# AT24C.net
KiCad netlist of a schematic drawn in Altium Designer
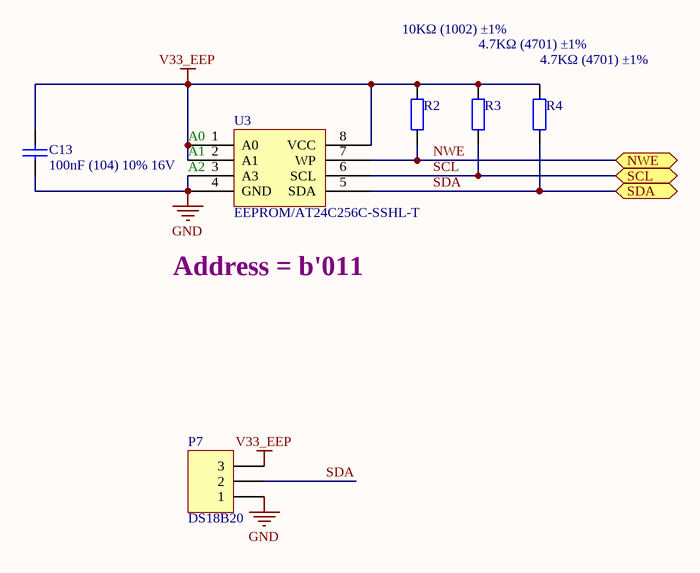
[diagram p0: AT24C.SchDoc]

(export (version "E")
  (design (tool "Eeschema 10.0.6"))
  (components
    (comp (ref "C13")
      (value "100nF (104) 10% 16V")
      (footprint "0402_C")
      (description "贴片电容")
      (libsource (lib "Miscellaneous Devices LC") (part "0402 100nF (104) 10% 16V"))
    )
    (comp (ref "P7")
      (value "DS18B20")
      (footprint "TO-92A")
      (description "Header, 3-Pin")
      (fields (field (name "PUBLISHER") "Altium Limited"))
      (libsource (lib "Miscellaneous Connectors") (part "Header 3"))
    )
    (comp (ref "R2")
      (value "10KΩ (1002) ±1%")
      (footprint "0402_R")
      (description "贴片电阻")
      (libsource (lib "Miscellaneous Devices LC") (part "0402 10KΩ (1002) 1%"))
    )
    (comp (ref "R3")
      (value "4.7KΩ (4701) ±1%")
      (footprint "0402_R")
      (description "贴片电阻")
      (libsource (lib "Miscellaneous Devices LC") (part "0402 4.7KΩ (4701) 1%"))
    )
    (comp (ref "R4")
      (value "4.7KΩ (4701) ±1%")
      (footprint "0402_R")
      (description "贴片电阻")
      (libsource (lib "Miscellaneous Devices LC") (part "0402 4.7KΩ (4701) 1%"))
    )
    (comp (ref "U3")
      (value "EEPROM/AT24C256C-SSHL-T")
      (footprint "SOIC-8_150mil")
      (description "EEPROM")
      (libsource (lib "Miscellaneous Devices LC") (part "EEPROM/AT24C256C-SSHL-T_[C6482]"))
    )
  )
  (nets
    (net (code "1") (name "/NWE") (class "Default")
      (node (ref "R2") (pin "1") (pinfunction "1_1") (pintype "passive"))
      (node (ref "U3") (pin "7") (pinfunction "WP_7") (pintype "passive"))
    )
    (net (code "2") (name "/SCL") (class "Default")
      (node (ref "R3") (pin "1") (pinfunction "1_1") (pintype "passive"))
      (node (ref "U3") (pin "6") (pinfunction "SCL_6") (pintype "passive"))
    )
    (net (code "3") (name "/SDA") (class "Default")
      (node (ref "P7") (pin "2") (pinfunction "2_2") (pintype "passive"))
      (node (ref "R4") (pin "1") (pinfunction "1_1") (pintype "passive"))
      (node (ref "U3") (pin "5") (pinfunction "SDA_5") (pintype "passive"))
    )
    (net (code "4") (name "GND") (class "Default")
      (node (ref "C13") (pin "1") (pinfunction "1_1") (pintype "passive"))
      (node (ref "P7") (pin "1") (pinfunction "1_1") (pintype "passive"))
      (node (ref "U3") (pin "3") (pinfunction "A3_3") (pintype "passive"))
      (node (ref "U3") (pin "4") (pinfunction "GND_4") (pintype "passive"))
    )
    (net (code "5") (name "V33_EEP") (class "Default")
      (node (ref "C13") (pin "2") (pinfunction "2_2") (pintype "passive"))
      (node (ref "P7") (pin "3") (pinfunction "3_3") (pintype "passive"))
      (node (ref "R2") (pin "2") (pinfunction "2_2") (pintype "passive"))
      (node (ref "R3") (pin "2") (pinfunction "2_2") (pintype "passive"))
      (node (ref "R4") (pin "2") (pinfunction "2_2") (pintype "passive"))
      (node (ref "U3") (pin "1") (pinfunction "A0_1") (pintype "passive"))
      (node (ref "U3") (pin "2") (pinfunction "A1_2") (pintype "passive"))
      (node (ref "U3") (pin "8") (pinfunction "VCC_8") (pintype "passive"))
    )
  )
)
